# pulsePreamplifier.net
KiCad netlist of a schematic drawn in Altium Designer
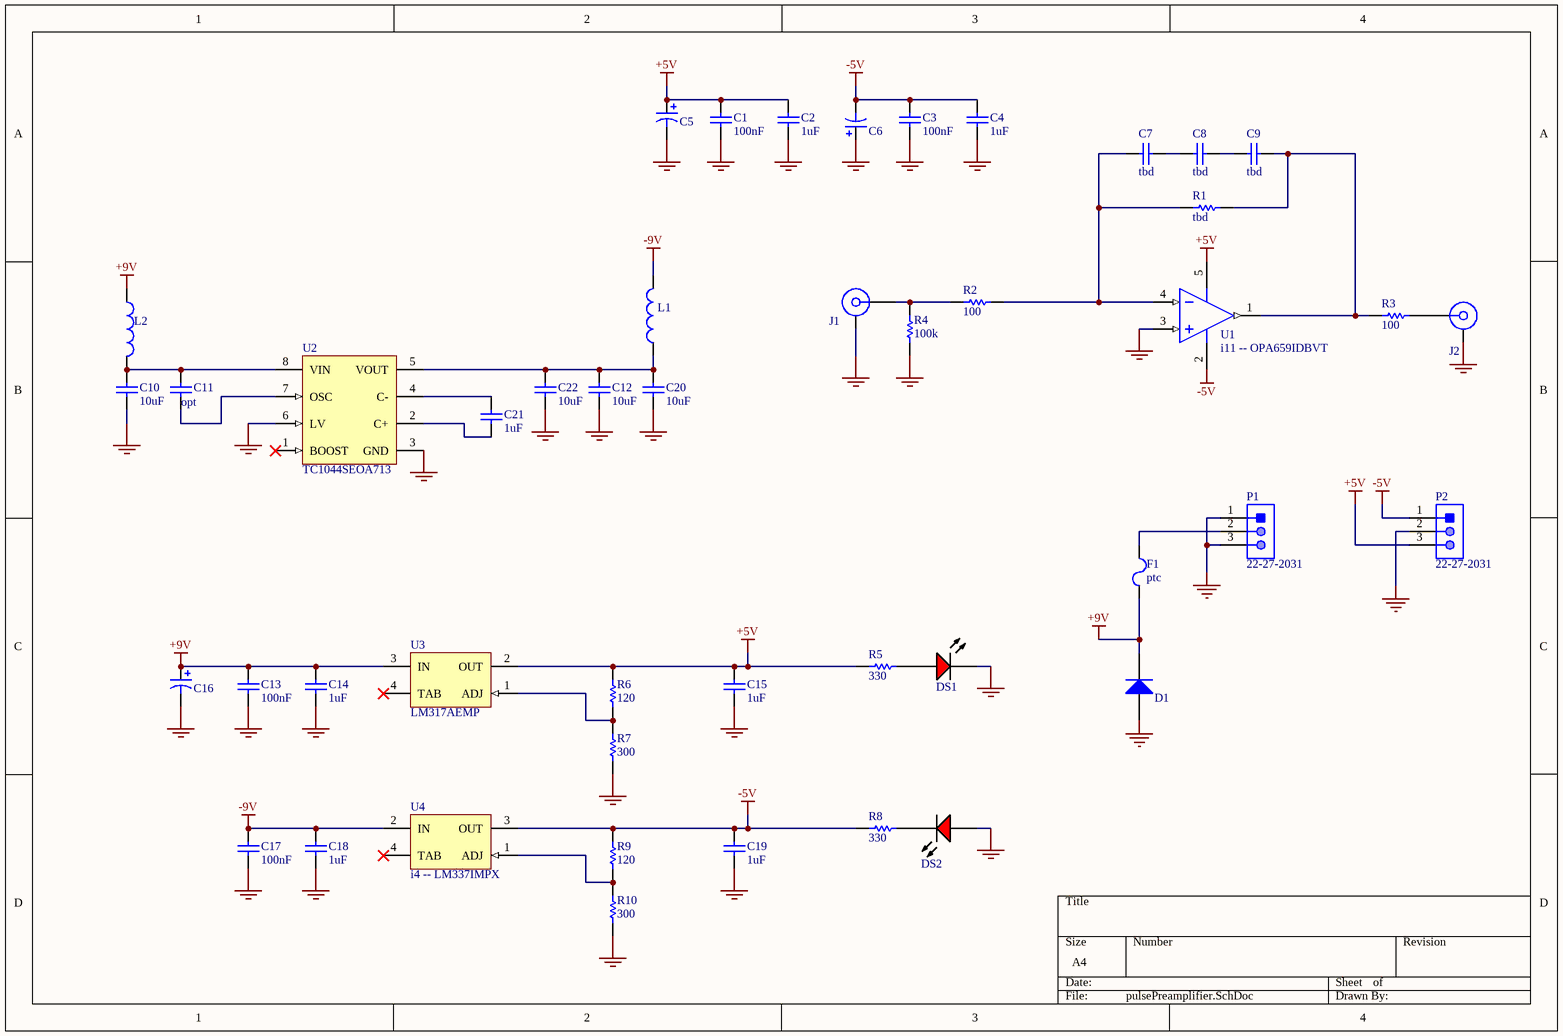
[diagram p0: pulsePreamplifier.SchDoc]

(export (version "E")
  (design (tool "Eeschema 10.0.6"))
  (components
    (comp (ref "C1")
      (value "100nF")
      (footprint "CAPC0603(1608)100_N")
      (description "CAP 100nF 25V ±20% 0603 (1608 Metric) Thickness 1mm SMD")
      (fields (field (name "TOLERANCE") "Â±20%"))
      (libsource (lib "Altium Content Vault") (part "CAP"))
    )
    (comp (ref "C2")
      (value "1uF")
      (footprint "CAPC0603(1608)100_N")
      (description "CAP 1uF 25V ±20% 0603 (1608 Metric) Thickness 1mm SMD")
      (fields (field (name "TOLERANCE") "Â±20%"))
      (libsource (lib "Altium Content Vault") (part "CAP"))
    )
    (comp (ref "C3")
      (value "100nF")
      (footprint "CAPC0603(1608)100_N")
      (description "CAP 100nF 25V ±20% 0603 (1608 Metric) Thickness 1mm SMD")
      (fields (field (name "TOLERANCE") "Â±20%"))
      (libsource (lib "Altium Content Vault") (part "CAP"))
    )
    (comp (ref "C4")
      (value "1uF")
      (footprint "CAPC0603(1608)100_N")
      (description "CAP 1uF 25V ±20% 0603 (1608 Metric) Thickness 1mm SMD")
      (fields (field (name "TOLERANCE") "Â±20%"))
      (libsource (lib "Altium Content Vault") (part "CAP"))
    )
    (comp (ref "C5")
      (value "ECA-1HM470")
      (footprint "PNSC-ECA-1HM470")
      (description "CAP ALUM 47UF 50V 20% RADIAL")
      (libsource (lib "Altium Content Vault") (part "CAP-P-2"))
    )
    (comp (ref "C6")
      (value "ECA-1HM470")
      (footprint "PNSC-ECA-1HM470")
      (description "CAP ALUM 47UF 50V 20% RADIAL")
      (libsource (lib "Altium Content Vault") (part "CAP-P-2"))
    )
    (comp (ref "C7")
      (value "tbd")
      (footprint "CAPC0603(1608)100_N")
      (description "CAP 1uF 25V ±20% 0603 (1608 Metric) Thickness 1mm SMD")
      (fields (field (name "TOLERANCE") "Â±20%"))
      (libsource (lib "Altium Content Vault") (part "CAP"))
    )
    (comp (ref "C8")
      (value "tbd")
      (footprint "CAPC0603(1608)100_N")
      (description "CAP 1uF 25V ±20% 0603 (1608 Metric) Thickness 1mm SMD")
      (fields (field (name "TOLERANCE") "Â±20%"))
      (libsource (lib "Altium Content Vault") (part "CAP"))
    )
    (comp (ref "C9")
      (value "tbd")
      (footprint "CAPC0603(1608)100_N")
      (description "CAP 1uF 25V ±20% 0603 (1608 Metric) Thickness 1mm SMD")
      (fields (field (name "TOLERANCE") "Â±20%"))
      (libsource (lib "Altium Content Vault") (part "CAP"))
    )
    (comp (ref "C10")
      (value "10uF")
      (footprint "CAPC1206(3216)190_N")
      (fields (field (name "TOLERANCE") "Â±20%"))
      (libsource (lib "Altium Content Vault") (part "CAP"))
    )
    (comp (ref "C11")
      (value "opt")
      (footprint "CAPC0603(1608)100_N")
      (description "CAP 1uF 25V ±20% 0603 (1608 Metric) Thickness 1mm SMD")
      (fields (field (name "TOLERANCE") "Â±20%"))
      (libsource (lib "Altium Content Vault") (part "CAP"))
    )
    (comp (ref "C12")
      (value "10uF")
      (footprint "CAPC1206(3216)190_N")
      (fields (field (name "TOLERANCE") "Â±20%"))
      (libsource (lib "Altium Content Vault") (part "CAP"))
    )
    (comp (ref "C13")
      (value "100nF")
      (footprint "CAPC0603(1608)100_N")
      (description "CAP 100nF 25V ±20% 0603 (1608 Metric) Thickness 1mm SMD")
      (fields (field (name "TOLERANCE") "Â±20%"))
      (libsource (lib "Altium Content Vault") (part "CAP"))
    )
    (comp (ref "C14")
      (value "1uF")
      (footprint "CAPC0603(1608)100_N")
      (description "CAP 1uF 25V ±20% 0603 (1608 Metric) Thickness 1mm SMD")
      (fields (field (name "TOLERANCE") "Â±20%"))
      (libsource (lib "Altium Content Vault") (part "CAP"))
    )
    (comp (ref "C15")
      (value "1uF")
      (footprint "CAPC0603(1608)100_N")
      (description "CAP 1uF 25V ±20% 0603 (1608 Metric) Thickness 1mm SMD")
      (fields (field (name "TOLERANCE") "Â±20%"))
      (libsource (lib "Altium Content Vault") (part "CAP"))
    )
    (comp (ref "C16")
      (value "ECA-1HM470")
      (footprint "PNSC-ECA-1HM470")
      (description "CAP ALUM 47UF 50V 20% RADIAL")
      (libsource (lib "Altium Content Vault") (part "CAP-P-2"))
    )
    (comp (ref "C17")
      (value "100nF")
      (footprint "CAPC0603(1608)100_N")
      (description "CAP 100nF 25V ±20% 0603 (1608 Metric) Thickness 1mm SMD")
      (fields (field (name "TOLERANCE") "Â±20%"))
      (libsource (lib "Altium Content Vault") (part "CAP"))
    )
    (comp (ref "C18")
      (value "1uF")
      (footprint "CAPC0603(1608)100_N")
      (description "CAP 1uF 25V ±20% 0603 (1608 Metric) Thickness 1mm SMD")
      (fields (field (name "TOLERANCE") "Â±20%"))
      (libsource (lib "Altium Content Vault") (part "CAP"))
    )
    (comp (ref "C19")
      (value "1uF")
      (footprint "CAPC0603(1608)100_N")
      (description "CAP 1uF 25V ±20% 0603 (1608 Metric) Thickness 1mm SMD")
      (fields (field (name "TOLERANCE") "Â±20%"))
      (libsource (lib "Altium Content Vault") (part "CAP"))
    )
    (comp (ref "C20")
      (value "10uF")
      (footprint "CAPC1206(3216)190_N")
      (fields (field (name "TOLERANCE") "Â±20%"))
      (libsource (lib "Altium Content Vault") (part "CAP"))
    )
    (comp (ref "C21")
      (value "1uF")
      (footprint "CAPC0603(1608)100_N")
      (description "CAP 1uF 25V ±20% 0603 (1608 Metric) Thickness 1mm SMD")
      (fields (field (name "TOLERANCE") "Â±20%"))
      (libsource (lib "Altium Content Vault") (part "CAP"))
    )
    (comp (ref "C22")
      (value "10uF")
      (footprint "CAPC1206(3216)190_N")
      (fields (field (name "TOLERANCE") "Â±20%"))
      (libsource (lib "Altium Content Vault") (part "CAP"))
    )
    (comp (ref "D1")
      (value "MMSD4148T3G")
      (footprint "ONSC-SOD123-2-425G-04_V")
      (description "Switching Diode, 100 V, 200 mA, -55 to 150 degC, 2-Pin SOD123 (425), RoHS, Tape and Reel")
      (fields (field (name "MANUFACTURER") "ON Semiconductor"))
      (libsource (lib "Altium Content Vault") (part "ONSC-MMSD4148-SOD123-2"))
    )
    (comp (ref "DS1")
      (value "TLMS1100-GS08")
      (footprint "VISH-TLMX1100_V")
      (description "LED, RED, 2.1 V, -40 to 100 degC, 2-Pin SMD (0603), RoHS, Tape and Reel")
      (fields (field (name "TOLERANCE") "5%"))
      (libsource (lib "Altium Content Vault") (part "LED-RED-AK-2"))
    )
    (comp (ref "DS2")
      (value "TLMS1100-GS08")
      (footprint "VISH-TLMX1100_V")
      (description "LED, RED, 2.1 V, -40 to 100 degC, 2-Pin SMD (0603), RoHS, Tape and Reel")
      (fields (field (name "TOLERANCE") "5%"))
      (libsource (lib "Altium Content Vault") (part "LED-RED-AK-2"))
    )
    (comp (ref "F1")
      (value "ptc")
      (footprint "LFUS-1206L012WR_V")
      (description "200mA PTC")
      (fields (field (name "MANUFACTURER") "Littelfuse"))
      (libsource (lib "Altium Content Vault") (part "FUSE-2"))
    )
    (comp (ref "J1")
      (value "32K145-400L5")
      (footprint "ROS-32K145-400L5_V")
      (description "SMA Right Angle Jack, Edge Mount, Up to 18 GHz, -55 to 155 degC")
      (fields (field (name "MANUFACTURER") "Rosenberger"))
      (libsource (lib "Altium Content Vault") (part "ROS-CN-1F-RF1-A"))
    )
    (comp (ref "J2")
      (value "32K145-400L5")
      (footprint "ROS-32K145-400L5_V")
      (description "SMA Right Angle Jack, Edge Mount, Up to 18 GHz, -55 to 155 degC")
      (fields (field (name "MANUFACTURER") "Rosenberger"))
      (libsource (lib "Altium Content Vault") (part "ROS-CN-1F-RF1-A"))
    )
    (comp (ref "L1")
      (value "FBMJ2125HM210NT")
      (footprint "INDC2013X105X50ML20T30")
      (description "Chip Inductor, 21 Ohm, +/- 30%, 6 A, -40 to 125 degC, 0805 (2012 Metric), RoHS, Tape and Reel")
      (fields (field (name "TOLERANCE") "30%"))
      (libsource (lib "Altium Content Vault") (part "IND-2"))
    )
    (comp (ref "L2")
      (value "FBMJ2125HM210NT")
      (footprint "INDC2013X105X50ML20T30")
      (description "Chip Inductor, 21 Ohm, +/- 30%, 6 A, -40 to 125 degC, 0805 (2012 Metric), RoHS, Tape and Reel")
      (fields (field (name "TOLERANCE") "30%"))
      (libsource (lib "Altium Content Vault") (part "IND-2"))
    )
    (comp (ref "P1")
      (value "22-27-2031")
      (footprint "MOLX-22-27-2031_V")
      (fields (field (name "MANUFACTURER") "Molex"))
      (libsource (lib "Altium Content Vault") (part "CN-1P-M-R3"))
    )
    (comp (ref "P2")
      (value "22-27-2031")
      (footprint "MOLX-22-27-2031_V")
      (fields (field (name "MANUFACTURER") "Molex"))
      (libsource (lib "Altium Content Vault") (part "CN-1P-M-R3"))
    )
    (comp (ref "R1")
      (value "tbd")
      (footprint "RESC0603(1608)_N")
      (description "100R 0.1W 1% 0603 (1608 Metric)  SMD")
      (fields (field (name "TOLERANCE") "1 %") (field (name "POWER") "0.1 W"))
      (libsource (lib "Altium Content Vault") (part "RES"))
    )
    (comp (ref "R2")
      (value "100")
      (footprint "RESC0603(1608)_N")
      (description "100R 0.1W 1% 0603 (1608 Metric)  SMD")
      (fields (field (name "TOLERANCE") "1 %") (field (name "POWER") "0.1 W"))
      (libsource (lib "Altium Content Vault") (part "RES"))
    )
    (comp (ref "R3")
      (value "100")
      (footprint "RESC0603(1608)_L")
      (description "100R 0.1W 1% 0603 (1608 Metric)  SMD")
      (fields (field (name "TOLERANCE") "1 %") (field (name "POWER") "0.1 W"))
      (libsource (lib "Altium Content Vault") (part "RES"))
    )
    (comp (ref "R4")
      (value "100k")
      (footprint "RESC0603(1608)_N")
      (description "100R 0.1W 1% 0603 (1608 Metric)  SMD")
      (fields (field (name "TOLERANCE") "1 %") (field (name "POWER") "0.1 W"))
      (libsource (lib "Altium Content Vault") (part "RES"))
    )
    (comp (ref "R5")
      (value "330")
      (footprint "RESC0603(1608)_N")
      (description "100R 0.1W 1% 0603 (1608 Metric)  SMD")
      (fields (field (name "TOLERANCE") "1 %") (field (name "POWER") "0.1 W"))
      (libsource (lib "Altium Content Vault") (part "RES"))
    )
    (comp (ref "R6")
      (value "120")
      (footprint "RESC0603(1608)_N")
      (description "100R 0.1W 1% 0603 (1608 Metric)  SMD")
      (fields (field (name "TOLERANCE") "1 %") (field (name "POWER") "0.1 W"))
      (libsource (lib "Altium Content Vault") (part "RES"))
    )
    (comp (ref "R7")
      (value "300")
      (footprint "RESC0603(1608)_N")
      (description "100R 0.1W 1% 0603 (1608 Metric)  SMD")
      (fields (field (name "TOLERANCE") "1 %") (field (name "POWER") "0.1 W"))
      (libsource (lib "Altium Content Vault") (part "RES"))
    )
    (comp (ref "R8")
      (value "330")
      (footprint "RESC0603(1608)_N")
      (description "100R 0.1W 1% 0603 (1608 Metric)  SMD")
      (fields (field (name "TOLERANCE") "1 %") (field (name "POWER") "0.1 W"))
      (libsource (lib "Altium Content Vault") (part "RES"))
    )
    (comp (ref "R9")
      (value "120")
      (footprint "RESC0603(1608)_N")
      (description "100R 0.1W 1% 0603 (1608 Metric)  SMD")
      (fields (field (name "TOLERANCE") "1 %") (field (name "POWER") "0.1 W"))
      (libsource (lib "Altium Content Vault") (part "RES"))
    )
    (comp (ref "R10")
      (value "300")
      (footprint "RESC0603(1608)_N")
      (description "100R 0.1W 1% 0603 (1608 Metric)  SMD")
      (fields (field (name "TOLERANCE") "1 %") (field (name "POWER") "0.1 W"))
      (libsource (lib "Altium Content Vault") (part "RES"))
    )
    (comp (ref "U1")
      (value "i11 -- OPA659IDBVT")
      (footprint "TI-DBV5_L")
      (fields (field (name "MANUFACTURER") "Texas Instruments") (field (name "PARTNUMBER") "OPA659IDBVT"))
      (libsource (lib "Altium Content Vault") (part "TI-AMP-S3-2-DBV5_A"))
    )
    (comp (ref "U2")
      (value "TC1044SEOA713")
      (footprint "SOIC-OA8_N")
      (description "Charge Pump DC-TO-DC Voltage Converter, 8-Pin SOIC 150mil, Industrial Temperature, Tape and Reel")
      (libsource (lib "Altium Content Vault") (part "PM-CHP-TC1044-IL8"))
    )
    (comp (ref "U3")
      (value "LM317AEMP")
      (footprint "DCY0004A_N")
      (description "3-Terminal Adjustable Regulator, 4-pin SOT-223")
      (fields (field (name "MANUFACTURER") "Texas Instruments"))
      (libsource (lib "Altium Content Vault") (part "PM-REG-LM317ADJ-SOT4"))
    )
    (comp (ref "U4")
      (value "i4 -- LM337IMPX")
      (footprint "MP04A_N")
      (description "3-Terminal Adjustable Negative Regulator, 4-pin SOT-223")
      (fields (field (name "MANUFACTURER") "National Semiconductor"))
      (libsource (lib "Altium Content Vault") (part "PM-REG-LM337ADJ-SOT4"))
    )
  )
  (nets
    (net (code "1") (name "+5V") (class "Default")
      (node (ref "C1") (pin "2") (pinfunction "2_2") (pintype "passive"))
      (node (ref "C15") (pin "2") (pinfunction "2_2") (pintype "passive"))
      (node (ref "C2") (pin "2") (pinfunction "2_2") (pintype "passive"))
      (node (ref "C5") (pin "1") (pinfunction "+_1") (pintype "passive"))
      (node (ref "P2") (pin "3") (pinfunction "3_3") (pintype "passive"))
      (node (ref "R5") (pin "1") (pinfunction "1_1") (pintype "passive"))
      (node (ref "R6") (pin "1") (pinfunction "1_1") (pintype "passive"))
      (node (ref "U1") (pin "5") (pinfunction "VS+_5") (pintype "power_in"))
      (node (ref "U3") (pin "2") (pinfunction "OUT_2") (pintype "power_in"))
    )
    (net (code "2") (name "+9V") (class "Default")
      (node (ref "C13") (pin "2") (pinfunction "2_2") (pintype "passive"))
      (node (ref "C14") (pin "2") (pinfunction "2_2") (pintype "passive"))
      (node (ref "C16") (pin "1") (pinfunction "+_1") (pintype "passive"))
      (node (ref "D1") (pin "1") (pinfunction "CATHODE_1") (pintype "passive"))
      (node (ref "F1") (pin "1") (pinfunction "1_1") (pintype "passive"))
      (node (ref "L2") (pin "1") (pinfunction "1_1") (pintype "passive"))
      (node (ref "U3") (pin "3") (pinfunction "IN_3") (pintype "power_in"))
    )
    (net (code "3") (name "-5V") (class "Default")
      (node (ref "C19") (pin "2") (pinfunction "2_2") (pintype "passive"))
      (node (ref "C3") (pin "2") (pinfunction "2_2") (pintype "passive"))
      (node (ref "C4") (pin "2") (pinfunction "2_2") (pintype "passive"))
      (node (ref "C6") (pin "2") (pinfunction "-_2") (pintype "passive"))
      (node (ref "P2") (pin "1") (pinfunction "1_1") (pintype "passive"))
      (node (ref "R8") (pin "1") (pinfunction "1_1") (pintype "passive"))
      (node (ref "R9") (pin "1") (pinfunction "1_1") (pintype "passive"))
      (node (ref "U1") (pin "2") (pinfunction "VS-_2") (pintype "power_in"))
      (node (ref "U4") (pin "3") (pinfunction "OUT_3") (pintype "power_in"))
    )
    (net (code "4") (name "-9V") (class "Default")
      (node (ref "C17") (pin "2") (pinfunction "2_2") (pintype "passive"))
      (node (ref "C18") (pin "2") (pinfunction "2_2") (pintype "passive"))
      (node (ref "L1") (pin "2") (pinfunction "2_2") (pintype "passive"))
      (node (ref "U4") (pin "2") (pinfunction "IN_2") (pintype "power_in"))
    )
    (net (code "5") (name "GND") (class "Default")
      (node (ref "C1") (pin "1") (pinfunction "1_1") (pintype "passive"))
      (node (ref "C10") (pin "1") (pinfunction "1_1") (pintype "passive"))
      (node (ref "C12") (pin "1") (pinfunction "1_1") (pintype "passive"))
      (node (ref "C13") (pin "1") (pinfunction "1_1") (pintype "passive"))
      (node (ref "C14") (pin "1") (pinfunction "1_1") (pintype "passive"))
      (node (ref "C15") (pin "1") (pinfunction "1_1") (pintype "passive"))
      (node (ref "C16") (pin "2") (pinfunction "-_2") (pintype "passive"))
      (node (ref "C17") (pin "1") (pinfunction "1_1") (pintype "passive"))
      (node (ref "C18") (pin "1") (pinfunction "1_1") (pintype "passive"))
      (node (ref "C19") (pin "1") (pinfunction "1_1") (pintype "passive"))
      (node (ref "C2") (pin "1") (pinfunction "1_1") (pintype "passive"))
      (node (ref "C20") (pin "1") (pinfunction "1_1") (pintype "passive"))
      (node (ref "C22") (pin "1") (pinfunction "1_1") (pintype "passive"))
      (node (ref "C3") (pin "1") (pinfunction "1_1") (pintype "passive"))
      (node (ref "C4") (pin "1") (pinfunction "1_1") (pintype "passive"))
      (node (ref "C5") (pin "2") (pinfunction "-_2") (pintype "passive"))
      (node (ref "C6") (pin "1") (pinfunction "+_1") (pintype "passive"))
      (node (ref "D1") (pin "2") (pinfunction "ANODE_2") (pintype "passive"))
      (node (ref "DS1") (pin "2") (pinfunction "K_2") (pintype "passive"))
      (node (ref "DS2") (pin "1") (pinfunction "A_1") (pintype "passive"))
      (node (ref "J1") (pin "MP") (pinfunction "MP_MP") (pintype "passive"))
      (node (ref "J2") (pin "MP") (pinfunction "MP_MP") (pintype "passive"))
      (node (ref "P1") (pin "1") (pinfunction "1_1") (pintype "passive"))
      (node (ref "P1") (pin "3") (pinfunction "3_3") (pintype "passive"))
      (node (ref "P2") (pin "2") (pinfunction "2_2") (pintype "passive"))
      (node (ref "R10") (pin "2") (pinfunction "2_2") (pintype "passive"))
      (node (ref "R4") (pin "1") (pinfunction "1_1") (pintype "passive"))
      (node (ref "R7") (pin "2") (pinfunction "2_2") (pintype "passive"))
      (node (ref "U1") (pin "3") (pinfunction "IN+_3") (pintype "input"))
      (node (ref "U2") (pin "3") (pinfunction "GND_3") (pintype "power_in"))
      (node (ref "U2") (pin "6") (pinfunction "LV_6") (pintype "input"))
    )
    (net (code "6") (name "Net-(C7-Pad1)") (class "Default")
      (node (ref "C7") (pin "1") (pinfunction "1_1") (pintype "passive"))
      (node (ref "C8") (pin "2") (pinfunction "2_2") (pintype "passive"))
    )
    (net (code "7") (name "Net-(C8-Pad1)") (class "Default")
      (node (ref "C8") (pin "1") (pinfunction "1_1") (pintype "passive"))
      (node (ref "C9") (pin "2") (pinfunction "2_2") (pintype "passive"))
    )
    (net (code "8") (name "Net-(DS1-A)") (class "Default")
      (node (ref "DS1") (pin "1") (pinfunction "A_1") (pintype "passive"))
      (node (ref "R5") (pin "2") (pinfunction "2_2") (pintype "passive"))
    )
    (net (code "9") (name "Net-(DS2-K)") (class "Default")
      (node (ref "DS2") (pin "2") (pinfunction "K_2") (pintype "passive"))
      (node (ref "R8") (pin "2") (pinfunction "2_2") (pintype "passive"))
    )
    (net (code "10") (name "Net-(F1-Pad2)") (class "Default")
      (node (ref "F1") (pin "2") (pinfunction "2_2") (pintype "passive"))
      (node (ref "P1") (pin "2") (pinfunction "2_2") (pintype "passive"))
    )
    (net (code "11") (name "Net-(J1-Pad1)") (class "Default")
      (node (ref "J1") (pin "1") (pinfunction "1_1") (pintype "passive"))
      (node (ref "R2") (pin "1") (pinfunction "1_1") (pintype "passive"))
      (node (ref "R4") (pin "2") (pinfunction "2_2") (pintype "passive"))
    )
    (net (code "12") (name "Net-(J2-Pad1)") (class "Default")
      (node (ref "J2") (pin "1") (pinfunction "1_1") (pintype "passive"))
      (node (ref "R3") (pin "2") (pinfunction "2_2") (pintype "passive"))
    )
    (net (code "13") (name "Net-(U1-IN-)") (class "Default")
      (node (ref "C7") (pin "2") (pinfunction "2_2") (pintype "passive"))
      (node (ref "R1") (pin "1") (pinfunction "1_1") (pintype "passive"))
      (node (ref "R2") (pin "2") (pinfunction "2_2") (pintype "passive"))
      (node (ref "U1") (pin "4") (pinfunction "IN-_4") (pintype "input"))
    )
    (net (code "14") (name "Net-(U1-OUT)") (class "Default")
      (node (ref "C9") (pin "1") (pinfunction "1_1") (pintype "passive"))
      (node (ref "R1") (pin "2") (pinfunction "2_2") (pintype "passive"))
      (node (ref "R3") (pin "1") (pinfunction "1_1") (pintype "passive"))
      (node (ref "U1") (pin "1") (pinfunction "OUT_1") (pintype "output"))
    )
    (net (code "15") (name "Net-(U2-C+)") (class "Default")
      (node (ref "C21") (pin "1") (pinfunction "1_1") (pintype "passive"))
      (node (ref "U2") (pin "2") (pinfunction "C+_2") (pintype "passive"))
    )
    (net (code "16") (name "Net-(U2-C-)") (class "Default")
      (node (ref "C21") (pin "2") (pinfunction "2_2") (pintype "passive"))
      (node (ref "U2") (pin "4") (pinfunction "C-_4") (pintype "passive"))
    )
    (net (code "17") (name "Net-(U2-OSC)") (class "Default")
      (node (ref "C11") (pin "1") (pinfunction "1_1") (pintype "passive"))
      (node (ref "U2") (pin "7") (pinfunction "OSC_7") (pintype "input"))
    )
    (net (code "18") (name "Net-(U2-VIN)") (class "Default")
      (node (ref "C10") (pin "2") (pinfunction "2_2") (pintype "passive"))
      (node (ref "C11") (pin "2") (pinfunction "2_2") (pintype "passive"))
      (node (ref "L2") (pin "2") (pinfunction "2_2") (pintype "passive"))
      (node (ref "U2") (pin "8") (pinfunction "VIN_8") (pintype "power_in"))
    )
    (net (code "19") (name "Net-(U2-VOUT)") (class "Default")
      (node (ref "C12") (pin "2") (pinfunction "2_2") (pintype "passive"))
      (node (ref "C20") (pin "2") (pinfunction "2_2") (pintype "passive"))
      (node (ref "C22") (pin "2") (pinfunction "2_2") (pintype "passive"))
      (node (ref "L1") (pin "1") (pinfunction "1_1") (pintype "passive"))
      (node (ref "U2") (pin "5") (pinfunction "VOUT_5") (pintype "power_in"))
    )
    (net (code "20") (name "Net-(U3-ADJ)") (class "Default")
      (node (ref "R6") (pin "2") (pinfunction "2_2") (pintype "passive"))
      (node (ref "R7") (pin "1") (pinfunction "1_1") (pintype "passive"))
      (node (ref "U3") (pin "1") (pinfunction "ADJ_1") (pintype "input"))
    )
    (net (code "21") (name "Net-(U4-ADJ)") (class "Default")
      (node (ref "R10") (pin "1") (pinfunction "1_1") (pintype "passive"))
      (node (ref "R9") (pin "2") (pinfunction "2_2") (pintype "passive"))
      (node (ref "U4") (pin "1") (pinfunction "ADJ_1") (pintype "input"))
    )
    (net (code "22") (name "unconnected-(U2-BOOST-Pad1)") (class "Default")
      (node (ref "U2") (pin "1") (pinfunction "BOOST_1") (pintype "input+no_connect"))
    )
    (net (code "23") (name "unconnected-(U3-TAB-Pad4)") (class "Default")
      (node (ref "U3") (pin "4") (pinfunction "TAB_4") (pintype "power_in+no_connect"))
    )
    (net (code "24") (name "unconnected-(U4-TAB-Pad4)") (class "Default")
      (node (ref "U4") (pin "4") (pinfunction "TAB_4") (pintype "power_in+no_connect"))
    )
  )
)
